# RGB_LED_Schematic.net
KiCad netlist of a schematic drawn in Altium Designer
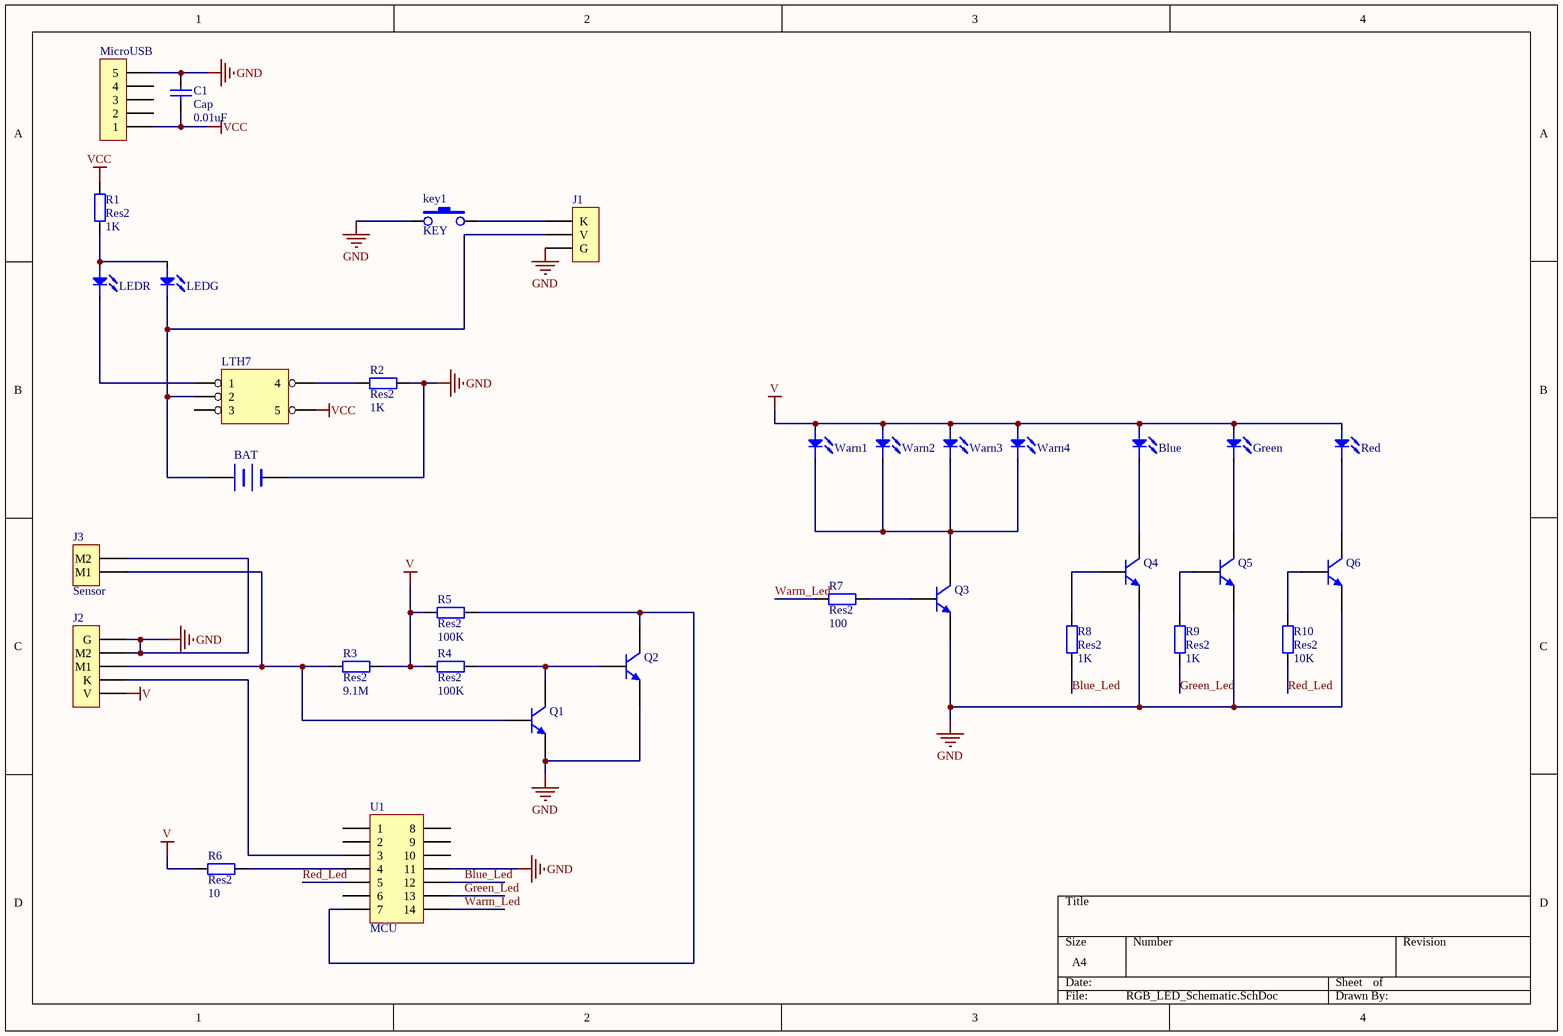
[diagram p0: RGB_LED_Schematic.SchDoc]

(export (version "E")
  (design (tool "Eeschema 10.0.6"))
  (components
    (comp (ref "BAT") (value "干电池") (description "Battery") (libsource (lib "干电池") (part "干电池")))
    (comp (ref "Blue") (value "LEDG") (footprint "LED") (libsource (lib "常用元件库") (part "LED")))
    (comp (ref "C1")
      (value "Cap")
      (footprint "RAD-0.3")
      (description "Capacitor")
      (fields (field (name "ALTIUM_VALUE") "0.01uF") (field (name "PUBLISHER") "Altium Limited"))
      (libsource (lib "Miscellaneous Devices") (part "Cap"))
    )
    (comp (ref "Green") (value "LEDG") (footprint "LED") (libsource (lib "常用元件库") (part "LED")))
    (comp (ref "J1") (value "CON3") (footprint "DG1283-5.0") (libsource (lib "常用元件库") (part "CON3")))
    (comp (ref "J2") (value "CON5") (footprint "DG1285-5.0") (libsource (lib "常用元件库") (part "CON5")))
    (comp (ref "J3") (value "Sensor") (description "Connector") (libsource (lib "杂元件库") (part "CON2")))
    (comp (ref "key1") (value "KEY") (footprint "AN12") (libsource (lib "常用元件库") (part "KEY")))
    (comp (ref "LEDG") (value "LEDG") (footprint "LED") (libsource (lib "常用元件库") (part "LED")))
    (comp (ref "LEDR") (value "LEDR") (footprint "LED") (libsource (lib "常用元件库") (part "LED")))
    (comp (ref "LTH7") (value "HEADER 3X2") (libsource (lib "Miscellaneous Devices") (part "HEADER 3X2")))
    (comp (ref "MicroUSB") (value "CON5") (footprint "DG1285-5.0") (libsource (lib "常用元件库") (part "CON5")))
    (comp (ref "Q1")
      (value "2N3904")
      (footprint "BCY-W3/E4")
      (description "NPN General Purpose Amplifier")
      (fields (field (name "PUBLISHER") "Altium Limited"))
      (libsource (lib "Miscellaneous Devices") (part "2N3904"))
    )
    (comp (ref "Q2")
      (value "2N3904")
      (footprint "BCY-W3/E4")
      (description "NPN General Purpose Amplifier")
      (fields (field (name "PUBLISHER") "Altium Limited"))
      (libsource (lib "Miscellaneous Devices") (part "2N3904"))
    )
    (comp (ref "Q3")
      (value "2N3904")
      (footprint "BCY-W3/E4")
      (description "NPN General Purpose Amplifier")
      (fields (field (name "PUBLISHER") "Altium Limited"))
      (libsource (lib "Miscellaneous Devices") (part "2N3904"))
    )
    (comp (ref "Q4")
      (value "2N3904")
      (footprint "BCY-W3/E4")
      (description "NPN General Purpose Amplifier")
      (fields (field (name "PUBLISHER") "Altium Limited"))
      (libsource (lib "Miscellaneous Devices") (part "2N3904"))
    )
    (comp (ref "Q5")
      (value "2N3904")
      (footprint "BCY-W3/E4")
      (description "NPN General Purpose Amplifier")
      (fields (field (name "PUBLISHER") "Altium Limited"))
      (libsource (lib "Miscellaneous Devices") (part "2N3904"))
    )
    (comp (ref "Q6")
      (value "2N3904")
      (footprint "BCY-W3/E4")
      (description "NPN General Purpose Amplifier")
      (fields (field (name "PUBLISHER") "Altium Limited"))
      (libsource (lib "Miscellaneous Devices") (part "2N3904"))
    )
    (comp (ref "R1")
      (value "Res2")
      (footprint "AXIAL-0.4")
      (description "Resistor")
      (fields (field (name "ALTIUM_VALUE") "1K") (field (name "PUBLISHER") "Altium Limited"))
      (libsource (lib "") (part "Res2_1"))
    )
    (comp (ref "R2")
      (value "Res2")
      (footprint "AXIAL-0.4")
      (description "Resistor")
      (fields (field (name "ALTIUM_VALUE") "1K") (field (name "PUBLISHER") "Altium Limited"))
      (libsource (lib "Miscellaneous Devices") (part "Res2"))
    )
    (comp (ref "R3")
      (value "Res2")
      (footprint "AXIAL-0.4")
      (description "Resistor")
      (fields (field (name "ALTIUM_VALUE") "9.1M") (field (name "PUBLISHER") "Altium Limited"))
      (libsource (lib "Miscellaneous Devices") (part "Res2"))
    )
    (comp (ref "R4")
      (value "Res2")
      (footprint "AXIAL-0.4")
      (description "Resistor")
      (fields (field (name "ALTIUM_VALUE") "100K") (field (name "PUBLISHER") "Altium Limited"))
      (libsource (lib "Miscellaneous Devices") (part "Res2"))
    )
    (comp (ref "R5")
      (value "Res2")
      (footprint "AXIAL-0.4")
      (description "Resistor")
      (fields (field (name "ALTIUM_VALUE") "100K") (field (name "PUBLISHER") "Altium Limited"))
      (libsource (lib "Miscellaneous Devices") (part "Res2"))
    )
    (comp (ref "R6")
      (value "Res2")
      (footprint "AXIAL-0.4")
      (description "Resistor")
      (fields (field (name "ALTIUM_VALUE") "10") (field (name "PUBLISHER") "Altium Limited"))
      (libsource (lib "Miscellaneous Devices") (part "Res2"))
    )
    (comp (ref "R7")
      (value "Res2")
      (footprint "AXIAL-0.4")
      (description "Resistor")
      (fields (field (name "ALTIUM_VALUE") "100") (field (name "PUBLISHER") "Altium Limited"))
      (libsource (lib "Miscellaneous Devices") (part "Res2"))
    )
    (comp (ref "R8")
      (value "Res2")
      (footprint "AXIAL-0.4")
      (description "Resistor")
      (fields (field (name "ALTIUM_VALUE") "1K") (field (name "PUBLISHER") "Altium Limited"))
      (libsource (lib "") (part "Res2_1"))
    )
    (comp (ref "R9")
      (value "Res2")
      (footprint "AXIAL-0.4")
      (description "Resistor")
      (fields (field (name "ALTIUM_VALUE") "1K") (field (name "PUBLISHER") "Altium Limited"))
      (libsource (lib "") (part "Res2_1"))
    )
    (comp (ref "R10")
      (value "Res2")
      (footprint "AXIAL-0.4")
      (description "Resistor")
      (fields (field (name "ALTIUM_VALUE") "10K") (field (name "PUBLISHER") "Altium Limited"))
      (libsource (lib "") (part "Res2_1"))
    )
    (comp (ref "Red") (value "LEDG") (footprint "LED") (libsource (lib "常用元件库") (part "LED")))
    (comp (ref "U1")
      (value "MCU")
      (footprint "HDR2X7_CEN")
      (description "Header, 7-Pin, Dual row")
      (fields (field (name "PUBLISHER") "Altium Limited"))
      (libsource (lib "Miscellaneous Connectors") (part "Header 7X2A"))
    )
    (comp (ref "Warn1") (value "LEDG") (footprint "LED") (libsource (lib "常用元件库") (part "LED")))
    (comp (ref "Warn2") (value "LEDG") (footprint "LED") (libsource (lib "常用元件库") (part "LED")))
    (comp (ref "Warn3") (value "LEDG") (footprint "LED") (libsource (lib "常用元件库") (part "LED")))
    (comp (ref "Warn4") (value "LEDG") (footprint "LED") (libsource (lib "常用元件库") (part "LED")))
  )
  (nets
    (net (code "1") (name "/Blue_Led") (class "Default")
      (node (ref "R8") (pin "1") (pinfunction "1_1") (pintype "passive"))
      (node (ref "U1") (pin "12") (pinfunction "12_12") (pintype "passive"))
    )
    (net (code "2") (name "/Green_Led") (class "Default")
      (node (ref "R9") (pin "1") (pinfunction "1_1") (pintype "passive"))
      (node (ref "U1") (pin "13") (pinfunction "13_13") (pintype "passive"))
    )
    (net (code "3") (name "/Red_Led") (class "Default")
      (node (ref "R10") (pin "1") (pinfunction "1_1") (pintype "passive"))
      (node (ref "U1") (pin "5") (pinfunction "5_5") (pintype "passive"))
    )
    (net (code "4") (name "/Warm_Led") (class "Default")
      (node (ref "R7") (pin "1") (pinfunction "1_1") (pintype "passive"))
      (node (ref "U1") (pin "14") (pinfunction "14_14") (pintype "passive"))
    )
    (net (code "5") (name "GND") (class "Default")
      (node (ref "BAT") (pin "2") (pinfunction "-_2") (pintype "passive"))
      (node (ref "C1") (pin "2") (pinfunction "2_2") (pintype "passive"))
      (node (ref "J1") (pin "3") (pinfunction "G_3") (pintype "passive"))
      (node (ref "J2") (pin "4") (pinfunction "4_4") (pintype "passive"))
      (node (ref "J2") (pin "5") (pinfunction "5_5") (pintype "passive"))
      (node (ref "J3") (pin "2") (pinfunction "M2_2") (pintype "passive"))
      (node (ref "MicroUSB") (pin "5") (pinfunction "5_5") (pintype "passive"))
      (node (ref "Q1") (pin "1") (pinfunction "E_1") (pintype "passive"))
      (node (ref "Q2") (pin "1") (pinfunction "E_1") (pintype "passive"))
      (node (ref "Q3") (pin "1") (pinfunction "E_1") (pintype "passive"))
      (node (ref "Q4") (pin "1") (pinfunction "E_1") (pintype "passive"))
      (node (ref "Q5") (pin "1") (pinfunction "E_1") (pintype "passive"))
      (node (ref "Q6") (pin "1") (pinfunction "E_1") (pintype "passive"))
      (node (ref "R2") (pin "2") (pinfunction "2_2") (pintype "passive"))
      (node (ref "U1") (pin "11") (pinfunction "11_11") (pintype "passive"))
      (node (ref "key1") (pin "1") (pinfunction "1_1") (pintype "passive"))
    )
    (net (code "6") (name "Net-(BAT-+)") (class "Default")
      (node (ref "BAT") (pin "1") (pinfunction "+_1") (pintype "passive"))
      (node (ref "J1") (pin "2") (pinfunction "V_2") (pintype "passive"))
      (node (ref "LEDG") (pin "K") (pintype "passive"))
      (node (ref "LTH7") (pin "3") (pinfunction "2_3") (pintype "passive"))
    )
    (net (code "7") (name "Net-(J1-K)") (class "Default")
      (node (ref "J1") (pin "1") (pinfunction "K_1") (pintype "passive"))
      (node (ref "key1") (pin "2") (pinfunction "2_2") (pintype "passive"))
    )
    (net (code "8") (name "Net-(J2-Pad2)") (class "Default")
      (node (ref "J2") (pin "2") (pinfunction "2_2") (pintype "passive"))
      (node (ref "U1") (pin "3") (pinfunction "3_3") (pintype "passive"))
    )
    (net (code "9") (name "Net-(J3-M1)") (class "Default")
      (node (ref "J2") (pin "3") (pinfunction "3_3") (pintype "passive"))
      (node (ref "J3") (pin "1") (pinfunction "M1_1") (pintype "passive"))
      (node (ref "Q1") (pin "2") (pinfunction "B_2") (pintype "passive"))
      (node (ref "R3") (pin "1") (pinfunction "1_1") (pintype "passive"))
    )
    (net (code "10") (name "Net-(LEDG-PadA)") (class "Default")
      (node (ref "LEDG") (pin "A") (pintype "passive"))
      (node (ref "LEDR") (pin "A") (pintype "passive"))
      (node (ref "R1") (pin "1") (pinfunction "1_1") (pintype "passive"))
    )
    (net (code "11") (name "Net-(LEDR-PadK)") (class "Default")
      (node (ref "LEDR") (pin "K") (pintype "passive"))
      (node (ref "LTH7") (pin "1") (pinfunction "1_1") (pintype "passive"))
    )
    (net (code "12") (name "Net-(LTH7-4-Pad2)") (class "Default")
      (node (ref "LTH7") (pin "2") (pinfunction "4_2") (pintype "passive"))
      (node (ref "R2") (pin "1") (pinfunction "1_1") (pintype "passive"))
    )
    (net (code "13") (name "Net-(Q1-C)") (class "Default")
      (node (ref "Q1") (pin "3") (pinfunction "C_3") (pintype "passive"))
      (node (ref "Q2") (pin "2") (pinfunction "B_2") (pintype "passive"))
      (node (ref "R4") (pin "2") (pinfunction "2_2") (pintype "passive"))
    )
    (net (code "14") (name "Net-(Q2-C)") (class "Default")
      (node (ref "Q2") (pin "3") (pinfunction "C_3") (pintype "passive"))
      (node (ref "R5") (pin "2") (pinfunction "2_2") (pintype "passive"))
      (node (ref "U1") (pin "7") (pinfunction "7_7") (pintype "passive"))
    )
    (net (code "15") (name "Net-(Q3-B)") (class "Default")
      (node (ref "Q3") (pin "2") (pinfunction "B_2") (pintype "passive"))
      (node (ref "R7") (pin "2") (pinfunction "2_2") (pintype "passive"))
    )
    (net (code "16") (name "Net-(Q3-C)") (class "Default")
      (node (ref "Q3") (pin "3") (pinfunction "C_3") (pintype "passive"))
      (node (ref "Warn1") (pin "K") (pintype "passive"))
      (node (ref "Warn2") (pin "K") (pintype "passive"))
      (node (ref "Warn3") (pin "K") (pintype "passive"))
      (node (ref "Warn4") (pin "K") (pintype "passive"))
    )
    (net (code "17") (name "Net-(Q4-B)") (class "Default")
      (node (ref "Q4") (pin "2") (pinfunction "B_2") (pintype "passive"))
      (node (ref "R8") (pin "2") (pinfunction "2_2") (pintype "passive"))
    )
    (net (code "18") (name "Net-(Q4-C)") (class "Default")
      (node (ref "Blue") (pin "K") (pintype "passive"))
      (node (ref "Q4") (pin "3") (pinfunction "C_3") (pintype "passive"))
    )
    (net (code "19") (name "Net-(Q5-B)") (class "Default")
      (node (ref "Q5") (pin "2") (pinfunction "B_2") (pintype "passive"))
      (node (ref "R9") (pin "2") (pinfunction "2_2") (pintype "passive"))
    )
    (net (code "20") (name "Net-(Q5-C)") (class "Default")
      (node (ref "Green") (pin "K") (pintype "passive"))
      (node (ref "Q5") (pin "3") (pinfunction "C_3") (pintype "passive"))
    )
    (net (code "21") (name "Net-(Q6-B)") (class "Default")
      (node (ref "Q6") (pin "2") (pinfunction "B_2") (pintype "passive"))
      (node (ref "R10") (pin "2") (pinfunction "2_2") (pintype "passive"))
    )
    (net (code "22") (name "Net-(Q6-C)") (class "Default")
      (node (ref "Q6") (pin "3") (pinfunction "C_3") (pintype "passive"))
      (node (ref "Red") (pin "K") (pintype "passive"))
    )
    (net (code "23") (name "Net-(R6-Pad2)") (class "Default")
      (node (ref "R6") (pin "2") (pinfunction "2_2") (pintype "passive"))
      (node (ref "U1") (pin "4") (pinfunction "4_4") (pintype "passive"))
    )
    (net (code "24") (name "V") (class "Default")
      (node (ref "Blue") (pin "A") (pintype "passive"))
      (node (ref "Green") (pin "A") (pintype "passive"))
      (node (ref "J2") (pin "1") (pinfunction "1_1") (pintype "passive"))
      (node (ref "R3") (pin "2") (pinfunction "2_2") (pintype "passive"))
      (node (ref "R4") (pin "1") (pinfunction "1_1") (pintype "passive"))
      (node (ref "R5") (pin "1") (pinfunction "1_1") (pintype "passive"))
      (node (ref "R6") (pin "1") (pinfunction "1_1") (pintype "passive"))
      (node (ref "Red") (pin "A") (pintype "passive"))
      (node (ref "Warn1") (pin "A") (pintype "passive"))
      (node (ref "Warn2") (pin "A") (pintype "passive"))
      (node (ref "Warn3") (pin "A") (pintype "passive"))
      (node (ref "Warn4") (pin "A") (pintype "passive"))
    )
    (net (code "25") (name "VCC") (class "Default")
      (node (ref "C1") (pin "1") (pinfunction "1_1") (pintype "passive"))
      (node (ref "LTH7") (pin "6") (pinfunction "5_6") (pintype "passive"))
      (node (ref "MicroUSB") (pin "1") (pinfunction "1_1") (pintype "passive"))
      (node (ref "R1") (pin "2") (pinfunction "2_2") (pintype "passive"))
    )
    (net (code "26") (name "unconnected-(LTH7-3-Pad5)") (class "Default")
      (node (ref "LTH7") (pin "5") (pinfunction "3_5") (pintype "passive"))
    )
    (net (code "27") (name "unconnected-(LTH7-Pad4)") (class "Default")
      (node (ref "LTH7") (pin "4") (pinfunction "4_4") (pintype "passive"))
    )
    (net (code "28") (name "unconnected-(MicroUSB-Pad2)") (class "Default")
      (node (ref "MicroUSB") (pin "2") (pinfunction "2_2") (pintype "passive"))
    )
    (net (code "29") (name "unconnected-(MicroUSB-Pad3)") (class "Default")
      (node (ref "MicroUSB") (pin "3") (pinfunction "3_3") (pintype "passive"))
    )
    (net (code "30") (name "unconnected-(MicroUSB-Pad4)") (class "Default")
      (node (ref "MicroUSB") (pin "4") (pinfunction "4_4") (pintype "passive"))
    )
    (net (code "31") (name "unconnected-(U1-Pad1)") (class "Default")
      (node (ref "U1") (pin "1") (pinfunction "1_1") (pintype "passive"))
    )
    (net (code "32") (name "unconnected-(U1-Pad2)") (class "Default")
      (node (ref "U1") (pin "2") (pinfunction "2_2") (pintype "passive"))
    )
    (net (code "33") (name "unconnected-(U1-Pad6)") (class "Default")
      (node (ref "U1") (pin "6") (pinfunction "6_6") (pintype "passive"))
    )
    (net (code "34") (name "unconnected-(U1-Pad8)") (class "Default")
      (node (ref "U1") (pin "8") (pinfunction "8_8") (pintype "passive"))
    )
    (net (code "35") (name "unconnected-(U1-Pad9)") (class "Default")
      (node (ref "U1") (pin "9") (pinfunction "9_9") (pintype "passive"))
    )
    (net (code "36") (name "unconnected-(U1-Pad10)") (class "Default")
      (node (ref "U1") (pin "10") (pinfunction "10_10") (pintype "passive"))
    )
  )
)
